# 120_01_ISC_BASE_BOARD.net
KiCad netlist of a schematic drawn in EAGLE
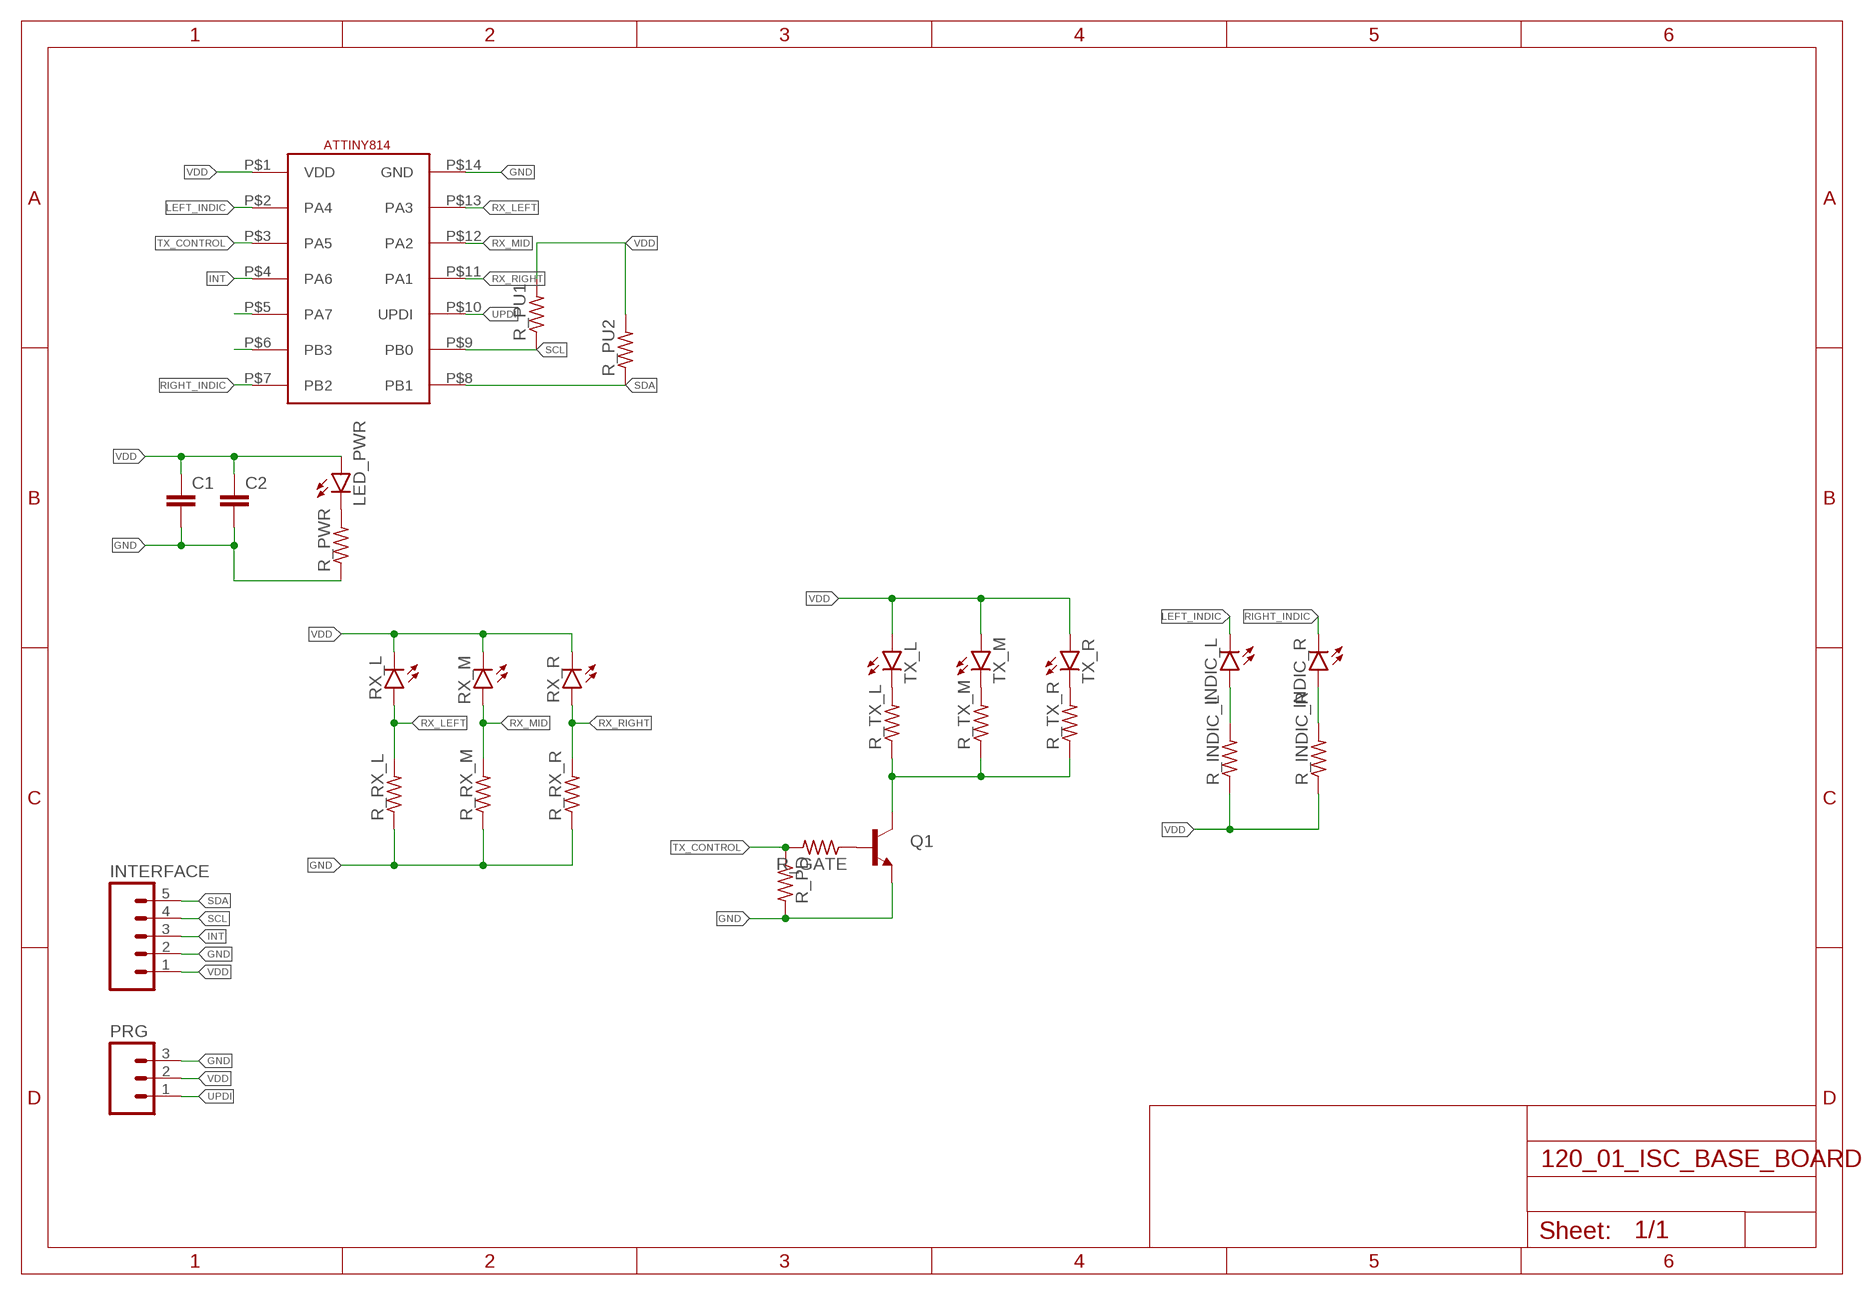
[diagram p0: schematic, sheet 1]

(export (version "E")
  (design (tool "Eeschema 10.0.6"))
  (components
    (comp (ref "C1")
      (value "C-EUC0805")
      (footprint "eagle-import:C0805")
      (libsource (lib "eagle-import") (part "C-EUC0805"))
    )
    (comp (ref "C2")
      (value "C-EUC0805")
      (footprint "eagle-import:C0805")
      (libsource (lib "eagle-import") (part "C-EUC0805"))
    )
    (comp (ref "INDIC_L")
      (value "LED3MM")
      (footprint "eagle-import:LED3MM")
      (libsource (lib "eagle-import") (part "LED3MM"))
    )
    (comp (ref "INDIC_R")
      (value "LED3MM")
      (footprint "eagle-import:LED3MM")
      (libsource (lib "eagle-import") (part "LED3MM"))
    )
    (comp (ref "INTERFACE")
      (value "M05NO_SILK")
      (footprint "eagle-import:1X05_NO_SILK")
      (libsource (lib "eagle-import") (part "M05NO_SILK"))
    )
    (comp (ref "LED_PWR")
      (value "LEDCHIP-LED0805")
      (footprint "eagle-import:CHIP-LED0805")
      (libsource (lib "eagle-import") (part "LEDCHIP-LED0805"))
    )
    (comp (ref "PRG")
      (value "M03PTH")
      (footprint "eagle-import:1X03")
      (libsource (lib "eagle-import") (part "M03PTH"))
    )
    (comp (ref "Q1")
      (value "TRANSISTOR_NPNBC547")
      (footprint "eagle-import:TO-92-AMMO")
      (libsource (lib "eagle-import") (part "TRANSISTOR_NPNBC547"))
    )
    (comp (ref "RX_L")
      (value "LED3MM")
      (footprint "eagle-import:LED3MM")
      (libsource (lib "eagle-import") (part "LED3MM"))
    )
    (comp (ref "RX_M")
      (value "LED3MM")
      (footprint "eagle-import:LED3MM")
      (libsource (lib "eagle-import") (part "LED3MM"))
    )
    (comp (ref "RX_R")
      (value "LED3MM")
      (footprint "eagle-import:LED3MM")
      (libsource (lib "eagle-import") (part "LED3MM"))
    )
    (comp (ref "R_GATE")
      (value "R-US_R0805")
      (footprint "eagle-import:R0805")
      (libsource (lib "eagle-import") (part "R-US_R0805"))
    )
    (comp (ref "R_INDIC_L")
      (value "R-US_R0805")
      (footprint "eagle-import:R0805")
      (libsource (lib "eagle-import") (part "R-US_R0805"))
    )
    (comp (ref "R_INDIC_R")
      (value "R-US_R0805")
      (footprint "eagle-import:R0805")
      (libsource (lib "eagle-import") (part "R-US_R0805"))
    )
    (comp (ref "R_PD")
      (value "R-US_R0805")
      (footprint "eagle-import:R0805")
      (libsource (lib "eagle-import") (part "R-US_R0805"))
    )
    (comp (ref "R_PU1")
      (value "R-US_R0805")
      (footprint "eagle-import:R0805")
      (libsource (lib "eagle-import") (part "R-US_R0805"))
    )
    (comp (ref "R_PU2")
      (value "R-US_R0805")
      (footprint "eagle-import:R0805")
      (libsource (lib "eagle-import") (part "R-US_R0805"))
    )
    (comp (ref "R_PWR")
      (value "R-US_R0805")
      (footprint "eagle-import:R0805")
      (libsource (lib "eagle-import") (part "R-US_R0805"))
    )
    (comp (ref "R_RX_L")
      (value "R-US_R0805")
      (footprint "eagle-import:R0805")
      (libsource (lib "eagle-import") (part "R-US_R0805"))
    )
    (comp (ref "R_RX_M")
      (value "R-US_R0805")
      (footprint "eagle-import:R0805")
      (libsource (lib "eagle-import") (part "R-US_R0805"))
    )
    (comp (ref "R_RX_R")
      (value "R-US_R0805")
      (footprint "eagle-import:R0805")
      (libsource (lib "eagle-import") (part "R-US_R0805"))
    )
    (comp (ref "R_TX_L")
      (value "R-US_R0805")
      (footprint "eagle-import:R0805")
      (libsource (lib "eagle-import") (part "R-US_R0805"))
    )
    (comp (ref "R_TX_M")
      (value "R-US_R0805")
      (footprint "eagle-import:R0805")
      (libsource (lib "eagle-import") (part "R-US_R0805"))
    )
    (comp (ref "R_TX_R")
      (value "R-US_R0805")
      (footprint "eagle-import:R0805")
      (libsource (lib "eagle-import") (part "R-US_R0805"))
    )
    (comp (ref "TX_L")
      (value "LED5MM")
      (footprint "eagle-import:LED5MM")
      (libsource (lib "eagle-import") (part "LED5MM"))
    )
    (comp (ref "TX_M")
      (value "LED5MM")
      (footprint "eagle-import:LED5MM")
      (libsource (lib "eagle-import") (part "LED5MM"))
    )
    (comp (ref "TX_R")
      (value "LED5MM")
      (footprint "eagle-import:LED5MM")
      (libsource (lib "eagle-import") (part "LED5MM"))
    )
    (comp (ref "U$1")
      (value "ATTINY814")
      (footprint "eagle-import:ATTINY814")
      (libsource (lib "eagle-import") (part "ATTINY814"))
    )
  )
  (nets
    (net (code "1") (name "GND") (class "Default")
      (node (ref "C1") (pin "2") (pinfunction "2_2") (pintype "passive"))
      (node (ref "C2") (pin "2") (pinfunction "2_2") (pintype "passive"))
      (node (ref "INTERFACE") (pin "2") (pinfunction "2_2") (pintype "passive"))
      (node (ref "PRG") (pin "3") (pinfunction "3_3") (pintype "passive"))
      (node (ref "Q1") (pin "3") (pinfunction "E_3") (pintype "passive"))
      (node (ref "R_PD") (pin "2") (pinfunction "2_2") (pintype "passive"))
      (node (ref "R_PWR") (pin "1") (pinfunction "1_1") (pintype "passive"))
      (node (ref "R_RX_L") (pin "1") (pinfunction "1_1") (pintype "passive"))
      (node (ref "R_RX_M") (pin "1") (pinfunction "1_1") (pintype "passive"))
      (node (ref "R_RX_R") (pin "1") (pinfunction "1_1") (pintype "passive"))
      (node (ref "U$1") (pin "P$14") (pinfunction "GND_P$14") (pintype "bidirectional"))
    )
    (net (code "2") (name "INT") (class "Default")
      (node (ref "INTERFACE") (pin "3") (pinfunction "3_3") (pintype "passive"))
      (node (ref "U$1") (pin "P$4") (pinfunction "PA6_P$4") (pintype "bidirectional"))
    )
    (net (code "3") (name "LEFT_INDIC") (class "Default")
      (node (ref "INDIC_L") (pin "K") (pinfunction "C_K") (pintype "passive"))
      (node (ref "U$1") (pin "P$2") (pinfunction "PA4_P$2") (pintype "bidirectional"))
    )
    (net (code "4") (name "Net-(INDIC_L-PadA)") (class "Default")
      (node (ref "INDIC_L") (pin "A") (pinfunction "A_A") (pintype "passive"))
      (node (ref "R_INDIC_L") (pin "2") (pinfunction "2_2") (pintype "passive"))
    )
    (net (code "5") (name "Net-(INDIC_R-PadA)") (class "Default")
      (node (ref "INDIC_R") (pin "A") (pinfunction "A_A") (pintype "passive"))
      (node (ref "R_INDIC_R") (pin "2") (pinfunction "2_2") (pintype "passive"))
    )
    (net (code "6") (name "Net-(LED_PWR-PadC)") (class "Default")
      (node (ref "LED_PWR") (pin "C") (pinfunction "C_C") (pintype "passive"))
      (node (ref "R_PWR") (pin "2") (pinfunction "2_2") (pintype "passive"))
    )
    (net (code "7") (name "Net-(Q1-B)") (class "Default")
      (node (ref "Q1") (pin "2") (pinfunction "B_2") (pintype "passive"))
      (node (ref "R_GATE") (pin "1") (pinfunction "1_1") (pintype "passive"))
    )
    (net (code "8") (name "Net-(Q1-C)") (class "Default")
      (node (ref "Q1") (pin "1") (pinfunction "C_1") (pintype "passive"))
      (node (ref "R_TX_L") (pin "1") (pinfunction "1_1") (pintype "passive"))
      (node (ref "R_TX_M") (pin "1") (pinfunction "1_1") (pintype "passive"))
      (node (ref "R_TX_R") (pin "1") (pinfunction "1_1") (pintype "passive"))
    )
    (net (code "9") (name "Net-(TX_L-C)") (class "Default")
      (node (ref "R_TX_L") (pin "2") (pinfunction "2_2") (pintype "passive"))
      (node (ref "TX_L") (pin "K") (pinfunction "C_K") (pintype "passive"))
    )
    (net (code "10") (name "Net-(TX_M-C)") (class "Default")
      (node (ref "R_TX_M") (pin "2") (pinfunction "2_2") (pintype "passive"))
      (node (ref "TX_M") (pin "K") (pinfunction "C_K") (pintype "passive"))
    )
    (net (code "11") (name "Net-(TX_R-C)") (class "Default")
      (node (ref "R_TX_R") (pin "2") (pinfunction "2_2") (pintype "passive"))
      (node (ref "TX_R") (pin "K") (pinfunction "C_K") (pintype "passive"))
    )
    (net (code "12") (name "RIGHT_INDIC") (class "Default")
      (node (ref "INDIC_R") (pin "K") (pinfunction "C_K") (pintype "passive"))
      (node (ref "U$1") (pin "P$7") (pinfunction "PB2_P$7") (pintype "bidirectional"))
    )
    (net (code "13") (name "RX_LEFT") (class "Default")
      (node (ref "RX_L") (pin "A") (pinfunction "A_A") (pintype "passive"))
      (node (ref "R_RX_L") (pin "2") (pinfunction "2_2") (pintype "passive"))
      (node (ref "U$1") (pin "P$13") (pinfunction "PA3_P$13") (pintype "bidirectional"))
    )
    (net (code "14") (name "RX_MID") (class "Default")
      (node (ref "RX_M") (pin "A") (pinfunction "A_A") (pintype "passive"))
      (node (ref "R_RX_M") (pin "2") (pinfunction "2_2") (pintype "passive"))
      (node (ref "U$1") (pin "P$12") (pinfunction "PA2_P$12") (pintype "bidirectional"))
    )
    (net (code "15") (name "RX_RIGHT") (class "Default")
      (node (ref "RX_R") (pin "A") (pinfunction "A_A") (pintype "passive"))
      (node (ref "R_RX_R") (pin "2") (pinfunction "2_2") (pintype "passive"))
      (node (ref "U$1") (pin "P$11") (pinfunction "PA1_P$11") (pintype "bidirectional"))
    )
    (net (code "16") (name "SCL") (class "Default")
      (node (ref "INTERFACE") (pin "4") (pinfunction "4_4") (pintype "passive"))
      (node (ref "R_PU1") (pin "1") (pinfunction "1_1") (pintype "passive"))
      (node (ref "U$1") (pin "P$9") (pinfunction "PB0_P$9") (pintype "bidirectional"))
    )
    (net (code "17") (name "SDA") (class "Default")
      (node (ref "INTERFACE") (pin "5") (pinfunction "5_5") (pintype "passive"))
      (node (ref "R_PU2") (pin "1") (pinfunction "1_1") (pintype "passive"))
      (node (ref "U$1") (pin "P$8") (pinfunction "PB1_P$8") (pintype "bidirectional"))
    )
    (net (code "18") (name "TX_CONTROL") (class "Default")
      (node (ref "R_GATE") (pin "2") (pinfunction "2_2") (pintype "passive"))
      (node (ref "R_PD") (pin "1") (pinfunction "1_1") (pintype "passive"))
      (node (ref "U$1") (pin "P$3") (pinfunction "PA5_P$3") (pintype "bidirectional"))
    )
    (net (code "19") (name "UPDI") (class "Default")
      (node (ref "PRG") (pin "1") (pinfunction "1_1") (pintype "passive"))
      (node (ref "U$1") (pin "P$10") (pinfunction "UPDI_P$10") (pintype "bidirectional"))
    )
    (net (code "20") (name "VDD") (class "Default")
      (node (ref "C1") (pin "1") (pinfunction "1_1") (pintype "passive"))
      (node (ref "C2") (pin "1") (pinfunction "1_1") (pintype "passive"))
      (node (ref "INTERFACE") (pin "1") (pinfunction "1_1") (pintype "passive"))
      (node (ref "LED_PWR") (pin "A") (pinfunction "A_A") (pintype "passive"))
      (node (ref "PRG") (pin "2") (pinfunction "2_2") (pintype "passive"))
      (node (ref "RX_L") (pin "K") (pinfunction "C_K") (pintype "passive"))
      (node (ref "RX_M") (pin "K") (pinfunction "C_K") (pintype "passive"))
      (node (ref "RX_R") (pin "K") (pinfunction "C_K") (pintype "passive"))
      (node (ref "R_INDIC_L") (pin "1") (pinfunction "1_1") (pintype "passive"))
      (node (ref "R_INDIC_R") (pin "1") (pinfunction "1_1") (pintype "passive"))
      (node (ref "R_PU1") (pin "2") (pinfunction "2_2") (pintype "passive"))
      (node (ref "R_PU2") (pin "2") (pinfunction "2_2") (pintype "passive"))
      (node (ref "TX_L") (pin "A") (pinfunction "A_A") (pintype "passive"))
      (node (ref "TX_M") (pin "A") (pinfunction "A_A") (pintype "passive"))
      (node (ref "TX_R") (pin "A") (pinfunction "A_A") (pintype "passive"))
      (node (ref "U$1") (pin "P$1") (pinfunction "VDD_P$1") (pintype "bidirectional"))
    )
    (net (code "21") (name "unconnected-(U$1-PA7-PadP$5)") (class "Default")
      (node (ref "U$1") (pin "P$5") (pinfunction "PA7_P$5") (pintype "bidirectional"))
    )
    (net (code "22") (name "unconnected-(U$1-PB3-PadP$6)") (class "Default")
      (node (ref "U$1") (pin "P$6") (pinfunction "PB3_P$6") (pintype "bidirectional"))
    )
  )
)
